# Comparator_Breakout_MCP6561.net
KiCad netlist of a schematic drawn in EAGLE
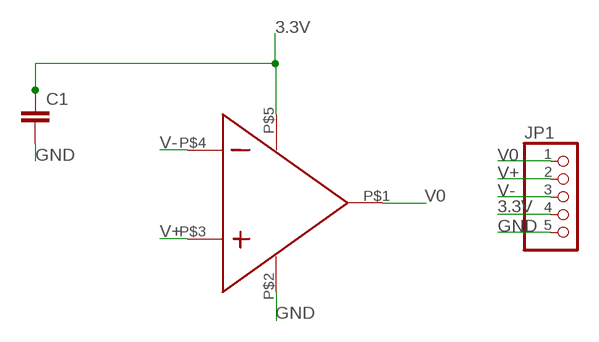
[diagram p0: schematic, sheet 1]

(export (version "E")
  (design (tool "Eeschema 10.0.6"))
  (components
    (comp (ref "C1")
      (value "C-EUC0805")
      (footprint "eagle-import:C0805")
      (libsource (lib "eagle-import") (part "C-EUC0805"))
    )
    (comp (ref "JP1")
      (value "PINHD-1X5")
      (footprint "eagle-import:1X05")
      (libsource (lib "eagle-import") (part "PINHD-1X5"))
    )
    (comp (ref "U$1")
      (value "MCP6561")
      (footprint "eagle-import:SC70-5")
      (libsource (lib "eagle-import") (part "MCP6561"))
    )
  )
  (nets
    (net (code "1") (name "/3.3V") (class "Default")
      (node (ref "C1") (pin "1") (pinfunction "1_1") (pintype "passive"))
      (node (ref "JP1") (pin "4") (pinfunction "4_4") (pintype "passive"))
      (node (ref "U$1") (pin "P$5") (pinfunction "VDD_P$5") (pintype "bidirectional"))
    )
    (net (code "2") (name "/GND") (class "Default")
      (node (ref "C1") (pin "2") (pinfunction "2_2") (pintype "passive"))
      (node (ref "JP1") (pin "5") (pinfunction "5_5") (pintype "passive"))
      (node (ref "U$1") (pin "P$2") (pinfunction "VSS_P$2") (pintype "bidirectional"))
    )
    (net (code "3") (name "/V+") (class "Default")
      (node (ref "JP1") (pin "2") (pinfunction "2_2") (pintype "passive"))
      (node (ref "U$1") (pin "P$3") (pinfunction "IN+_P$3") (pintype "bidirectional"))
    )
    (net (code "4") (name "/V-") (class "Default")
      (node (ref "JP1") (pin "3") (pinfunction "3_3") (pintype "passive"))
      (node (ref "U$1") (pin "P$4") (pinfunction "IN-_P$4") (pintype "bidirectional"))
    )
    (net (code "5") (name "/V0") (class "Default")
      (node (ref "JP1") (pin "1") (pinfunction "1_1") (pintype "passive"))
      (node (ref "U$1") (pin "P$1") (pinfunction "OUT_P$1") (pintype "bidirectional"))
    )
  )
)
